# splitter.net
KiCad netlist of a schematic drawn in EAGLE
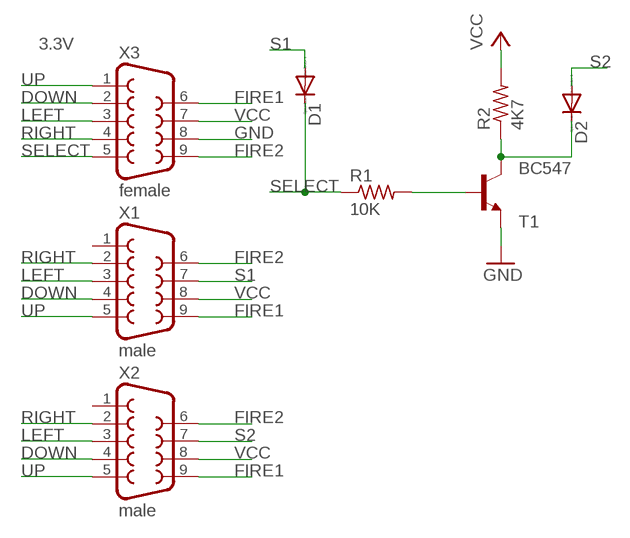
[diagram p0: schematic, sheet 1]

(export (version "E")
  (design (tool "Eeschema 10.0.6"))
  (components
    (comp (ref "D1")
      (value "1N4148DO35-7")
      (footprint "eagle-import:DO35-7")
      (libsource (lib "eagle-import") (part "1N4148DO35-7"))
    )
    (comp (ref "D2")
      (value "1N4148DO35-7")
      (footprint "eagle-import:DO35-7")
      (libsource (lib "eagle-import") (part "1N4148DO35-7"))
    )
    (comp (ref "R1")
      (value "10K")
      (footprint "eagle-import:0204_7")
      (libsource (lib "eagle-import") (part "R-US_0204/7"))
    )
    (comp (ref "R2")
      (value "4K7")
      (footprint "eagle-import:0204_7")
      (libsource (lib "eagle-import") (part "R-US_0204/7"))
    )
    (comp (ref "T1")
      (value "BC547")
      (footprint "eagle-import:TO92")
      (libsource (lib "eagle-import") (part "BC547"))
    )
    (comp (ref "X1")
      (value "male")
      (footprint "eagle-import:F09D")
      (libsource (lib "eagle-import") (part "F09D"))
    )
    (comp (ref "X2")
      (value "male")
      (footprint "eagle-import:F09D")
      (libsource (lib "eagle-import") (part "F09D"))
    )
    (comp (ref "X3")
      (value "female")
      (footprint "eagle-import:F09D")
      (libsource (lib "eagle-import") (part "F09D"))
    )
  )
  (nets
    (net (code "2") (name "/DOWN") (class "Default")
      (node (ref "X1") (pin "4") (pinfunction "4_4") (pintype "passive"))
      (node (ref "X2") (pin "4") (pinfunction "4_4") (pintype "passive"))
      (node (ref "X3") (pin "2") (pinfunction "2_2") (pintype "passive"))
    )
    (net (code "3") (name "/FIRE1") (class "Default")
      (node (ref "X1") (pin "9") (pinfunction "9_9") (pintype "passive"))
      (node (ref "X2") (pin "9") (pinfunction "9_9") (pintype "passive"))
      (node (ref "X3") (pin "6") (pinfunction "6_6") (pintype "passive"))
    )
    (net (code "4") (name "/FIRE2") (class "Default")
      (node (ref "X1") (pin "6") (pinfunction "6_6") (pintype "passive"))
      (node (ref "X2") (pin "6") (pinfunction "6_6") (pintype "passive"))
      (node (ref "X3") (pin "9") (pinfunction "9_9") (pintype "passive"))
    )
    (net (code "5") (name "/LEFT") (class "Default")
      (node (ref "X1") (pin "3") (pinfunction "3_3") (pintype "passive"))
      (node (ref "X2") (pin "3") (pinfunction "3_3") (pintype "passive"))
      (node (ref "X3") (pin "3") (pinfunction "3_3") (pintype "passive"))
    )
    (net (code "6") (name "/RIGHT") (class "Default")
      (node (ref "X1") (pin "2") (pinfunction "2_2") (pintype "passive"))
      (node (ref "X2") (pin "2") (pinfunction "2_2") (pintype "passive"))
      (node (ref "X3") (pin "4") (pinfunction "4_4") (pintype "passive"))
    )
    (net (code "7") (name "/S1") (class "Default")
      (node (ref "D1") (pin "A") (pinfunction "A_A") (pintype "passive"))
      (node (ref "X1") (pin "7") (pinfunction "7_7") (pintype "passive"))
    )
    (net (code "8") (name "/S2") (class "Default")
      (node (ref "D2") (pin "A") (pinfunction "A_A") (pintype "passive"))
      (node (ref "X2") (pin "7") (pinfunction "7_7") (pintype "passive"))
    )
    (net (code "9") (name "/SELECT") (class "Default")
      (node (ref "D1") (pin "C") (pinfunction "C_C") (pintype "passive"))
      (node (ref "R1") (pin "1") (pinfunction "1_1") (pintype "passive"))
      (node (ref "X3") (pin "5") (pinfunction "5_5") (pintype "passive"))
    )
    (net (code "10") (name "/UP") (class "Default")
      (node (ref "X1") (pin "5") (pinfunction "5_5") (pintype "passive"))
      (node (ref "X2") (pin "5") (pinfunction "5_5") (pintype "passive"))
      (node (ref "X3") (pin "1") (pinfunction "1_1") (pintype "passive"))
    )
    (net (code "11") (name "GND") (class "Default")
      (node (ref "T1") (pin "1") (pinfunction "E_1") (pintype "passive"))
      (node (ref "X3") (pin "8") (pinfunction "8_8") (pintype "passive"))
    )
    (net (code "12") (name "Net-(T1-B)") (class "Default")
      (node (ref "R1") (pin "2") (pinfunction "2_2") (pintype "passive"))
      (node (ref "T1") (pin "2") (pinfunction "B_2") (pintype "passive"))
    )
    (net (code "13") (name "Net-(T1-C)") (class "Default")
      (node (ref "D2") (pin "C") (pinfunction "C_C") (pintype "passive"))
      (node (ref "R2") (pin "1") (pinfunction "1_1") (pintype "passive"))
      (node (ref "T1") (pin "3") (pinfunction "C_3") (pintype "passive"))
    )
    (net (code "14") (name "VCC") (class "Default")
      (node (ref "R2") (pin "2") (pinfunction "2_2") (pintype "passive"))
      (node (ref "X1") (pin "8") (pinfunction "8_8") (pintype "passive"))
      (node (ref "X2") (pin "8") (pinfunction "8_8") (pintype "passive"))
      (node (ref "X3") (pin "7") (pinfunction "7_7") (pintype "passive"))
    )
    (net (code "15") (name "unconnected-(X1-Pad1)") (class "Default")
      (node (ref "X1") (pin "1") (pinfunction "1_1") (pintype "passive"))
    )
    (net (code "16") (name "unconnected-(X2-Pad1)") (class "Default")
      (node (ref "X2") (pin "1") (pinfunction "1_1") (pintype "passive"))
    )
  )
)
